# Sheet.net
KiCad netlist of a schematic drawn in Altium Designer
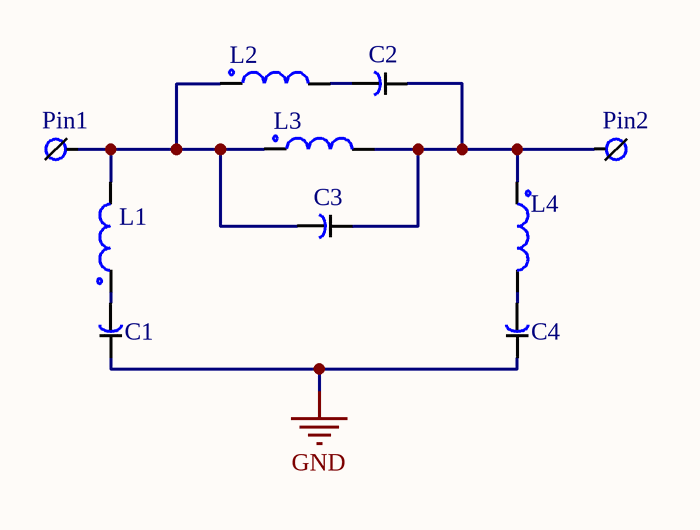
[diagram p0: Sheet.SchDoc]

(export (version "E")
  (design (tool "Eeschema 10.0.6"))
  (components
    (comp (ref "C1") (value "C1,C4") (footprint "C1,C4(0805)") (libsource (lib "Schlib") (part "C1,C4")))
    (comp (ref "C2") (value "C2") (footprint "C2(0603)") (libsource (lib "Schlib") (part "C2")))
    (comp (ref "C3") (value "C3") (footprint "C3(1206)") (libsource (lib "Schlib") (part "C3")))
    (comp (ref "C4") (value "C1,C4") (footprint "C1,C4(0805)") (libsource (lib "Schlib") (part "C1,C4")))
    (comp (ref "L1") (value "L1,L4,L3") (footprint "L1,L4,L3") (libsource (lib "Schlib") (part "L1,L4,L3")))
    (comp (ref "L2") (value "L2") (footprint "L2") (libsource (lib "Schlib") (part "L2")))
    (comp (ref "L3") (value "L1,L4,L3") (footprint "L1,L4,L3") (libsource (lib "Schlib") (part "L1,L4,L3")))
    (comp (ref "L4") (value "L1,L4,L3") (footprint "L1,L4,L3") (libsource (lib "Schlib") (part "L1,L4,L3")))
    (comp (ref "Pin1") (value "Comment") (footprint "Pin") (libsource (lib "Schlib") (part "Pin")))
    (comp (ref "Pin2") (value "Pin") (footprint "Pin") (libsource (lib "Schlib") (part "Pin")))
  )
  (nets
    (net (code "1") (name "GND") (class "Default")
      (node (ref "C1") (pin "2") (pinfunction "2_2") (pintype "passive"))
      (node (ref "C4") (pin "2") (pinfunction "2_2") (pintype "passive"))
    )
    (net (code "2") (name "Net-(C1-Pad1)") (class "Default")
      (node (ref "C1") (pin "1") (pinfunction "1_1") (pintype "passive"))
      (node (ref "L1") (pin "1") (pinfunction "1_1") (pintype "passive"))
    )
    (net (code "3") (name "Net-(C2-Pad1)") (class "Default")
      (node (ref "C2") (pin "1") (pinfunction "1_1") (pintype "passive"))
      (node (ref "L2") (pin "2") (pinfunction "2_2") (pintype "passive"))
    )
    (net (code "4") (name "Net-(C4-Pad1)") (class "Default")
      (node (ref "C4") (pin "1") (pinfunction "1_1") (pintype "passive"))
      (node (ref "L4") (pin "2") (pinfunction "2_2") (pintype "passive"))
    )
    (net (code "5") (name "Net-(Pin1-4)") (class "Default")
      (node (ref "C3") (pin "1") (pinfunction "1_1") (pintype "passive"))
      (node (ref "L1") (pin "2") (pinfunction "2_2") (pintype "passive"))
      (node (ref "L2") (pin "1") (pinfunction "1_1") (pintype "passive"))
      (node (ref "L3") (pin "1") (pinfunction "1_1") (pintype "passive"))
      (node (ref "Pin1") (pin "1") (pinfunction "4_1") (pintype "passive"))
    )
    (net (code "6") (name "Net-(Pin2-4)") (class "Default")
      (node (ref "C2") (pin "2") (pinfunction "2_2") (pintype "passive"))
      (node (ref "C3") (pin "2") (pinfunction "2_2") (pintype "passive"))
      (node (ref "L3") (pin "2") (pinfunction "2_2") (pintype "passive"))
      (node (ref "L4") (pin "1") (pinfunction "1_1") (pintype "passive"))
      (node (ref "Pin2") (pin "1") (pinfunction "4_1") (pintype "passive"))
    )
  )
)
